# Acoustics_Power.net
KiCad netlist of a schematic drawn in Altium Designer
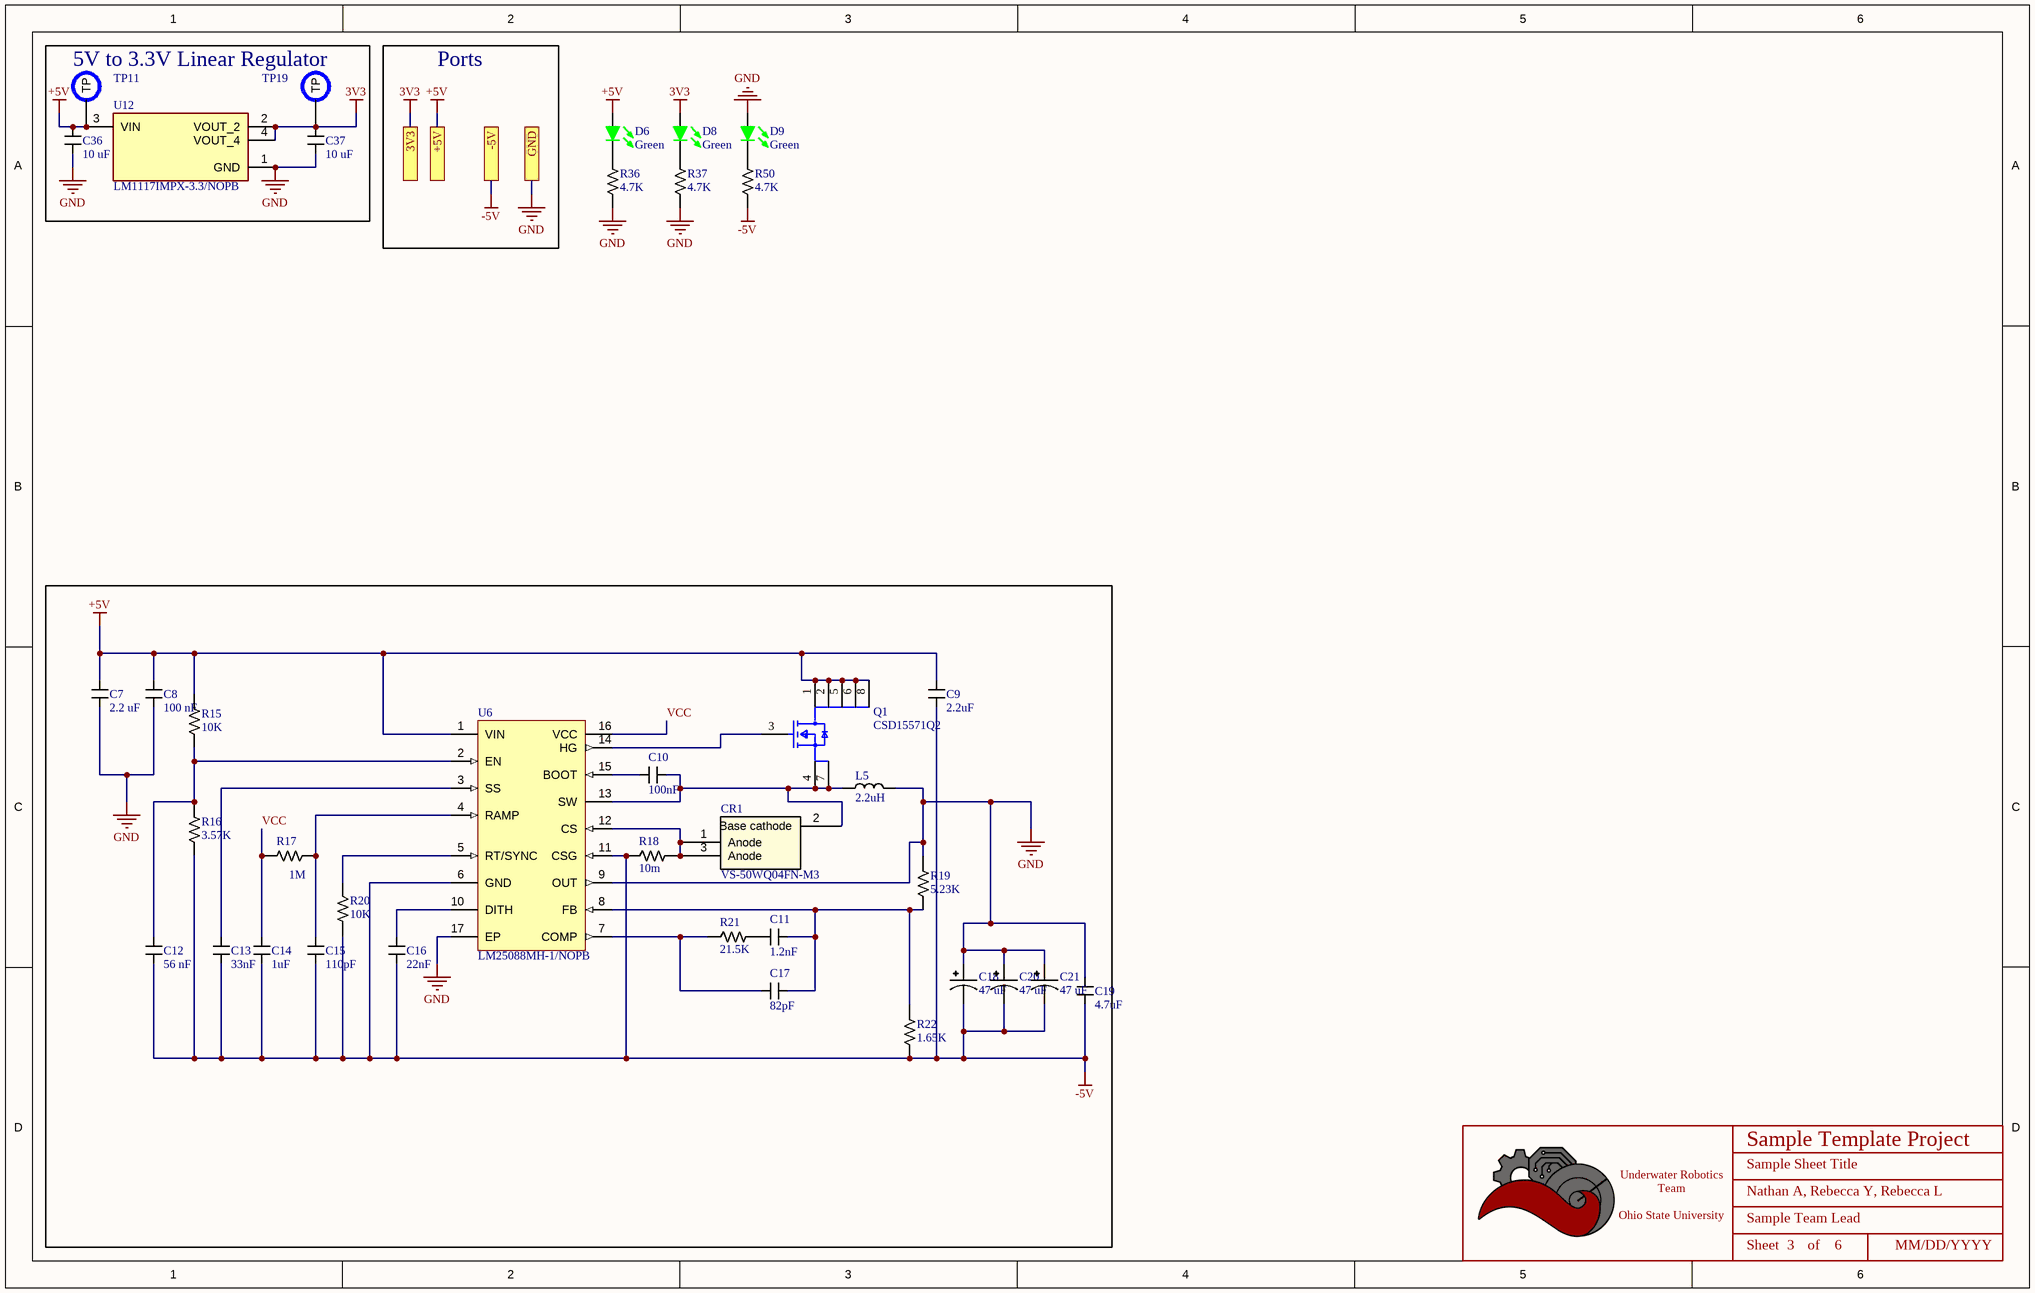
[diagram p0: [Acoustics] Power.SchDoc]

(export (version "E")
  (design (tool "Eeschema 10.0.6"))
  (components
    (comp (ref "C7")
      (value "2.2 uF")
      (footprint "CAPACITOR_0402")
      (description "Cap 1uF 16V +/-10%\r\nCeramic 0402")
      (fields
        (field (name "TOLERANCE") "+/- 10%")
        (field (name "VOLTAGE") "16V")
        (field (name "MADE BY") "Robert Pafford")
      )
      (libsource (lib "Capacitors") (part "CAPACITOR_1uF_0402"))
    )
    (comp (ref "C8")
      (value "100 nF")
      (footprint "CAPACITOR_0402")
      (description "Cap 1uF 16V +/-10%\r\nCeramic 0402")
      (fields
        (field (name "TOLERANCE") "+/- 10%")
        (field (name "VOLTAGE") "16V")
        (field (name "MADE BY") "Robert Pafford")
      )
      (libsource (lib "Capacitors") (part "CAPACITOR_1uF_0402"))
    )
    (comp (ref "C9")
      (value "2.2uF")
      (footprint "CAPACITOR_0402")
      (description "Cap 1uF 16V +/-10%\r\nCeramic 0402")
      (fields
        (field (name "TOLERANCE") "+/- 10%")
        (field (name "VOLTAGE") "16V")
        (field (name "MADE BY") "Robert Pafford")
      )
      (libsource (lib "Capacitors") (part "CAPACITOR_1uF_0402"))
    )
    (comp (ref "C10")
      (value "100nF")
      (footprint "CAPACITOR_0402")
      (description "Cap 1uF 16V +/-10%\r\nCeramic 0402")
      (fields
        (field (name "TOLERANCE") "+/- 10%")
        (field (name "VOLTAGE") "16V")
        (field (name "MADE BY") "Robert Pafford")
      )
      (libsource (lib "Capacitors") (part "CAPACITOR_1uF_0402"))
    )
    (comp (ref "C11")
      (value "1.2nF")
      (footprint "CAPACITOR_0402")
      (description "Cap 1uF 16V +/-10%\r\nCeramic 0402")
      (fields
        (field (name "TOLERANCE") "+/- 10%")
        (field (name "VOLTAGE") "16V")
        (field (name "MADE BY") "Robert Pafford")
      )
      (libsource (lib "Capacitors") (part "CAPACITOR_1uF_0402"))
    )
    (comp (ref "C12")
      (value "56 nF")
      (footprint "CAPACITOR_0402")
      (description "Cap 1uF 16V +/-10%\r\nCeramic 0402")
      (fields
        (field (name "TOLERANCE") "+/- 10%")
        (field (name "VOLTAGE") "16V")
        (field (name "MADE BY") "Robert Pafford")
      )
      (libsource (lib "Capacitors") (part "CAPACITOR_1uF_0402"))
    )
    (comp (ref "C13")
      (value "33nF")
      (footprint "CAPACITOR_0402")
      (description "Cap 1uF 16V +/-10%\r\nCeramic 0402")
      (fields
        (field (name "TOLERANCE") "+/- 10%")
        (field (name "VOLTAGE") "16V")
        (field (name "MADE BY") "Robert Pafford")
      )
      (libsource (lib "Capacitors") (part "CAPACITOR_1uF_0402"))
    )
    (comp (ref "C14")
      (value "1uF")
      (footprint "CAPACITOR_0402")
      (description "Cap 1uF 16V +/-10%\r\nCeramic 0402")
      (fields
        (field (name "TOLERANCE") "+/- 10%")
        (field (name "VOLTAGE") "16V")
        (field (name "MADE BY") "Robert Pafford")
      )
      (libsource (lib "Capacitors") (part "CAPACITOR_1uF_0402"))
    )
    (comp (ref "C15")
      (value "110pF")
      (footprint "CAPACITOR_0402")
      (description "Cap 1uF 16V +/-10%\r\nCeramic 0402")
      (fields
        (field (name "TOLERANCE") "+/- 10%")
        (field (name "VOLTAGE") "16V")
        (field (name "MADE BY") "Robert Pafford")
      )
      (libsource (lib "Capacitors") (part "CAPACITOR_1uF_0402"))
    )
    (comp (ref "C16")
      (value "22nF")
      (footprint "CAPACITOR_0402")
      (description "Cap 1uF 16V +/-10%\r\nCeramic 0402")
      (fields
        (field (name "TOLERANCE") "+/- 10%")
        (field (name "VOLTAGE") "16V")
        (field (name "MADE BY") "Robert Pafford")
      )
      (libsource (lib "Capacitors") (part "CAPACITOR_1uF_0402"))
    )
    (comp (ref "C17")
      (value "82pF")
      (footprint "CAPACITOR_0402")
      (description "Cap 1uF 16V +/-10%\r\nCeramic 0402")
      (fields
        (field (name "TOLERANCE") "+/- 10%")
        (field (name "VOLTAGE") "16V")
        (field (name "MADE BY") "Robert Pafford")
      )
      (libsource (lib "Capacitors") (part "CAPACITOR_1uF_0402"))
    )
    (comp (ref "C18")
      (value "10uF Tantalum 16V")
      (footprint "CAPACITOR_1206 - POLAR")
      (description "Cap 10uF 16V +/-20%\r\nTantalum 1206")
      (fields
        (field (name "TOLERANCE") "+/- 10%")
        (field (name "VOLTAGE") "16V")
        (field (name "VALUE (UF)") "47 uF")
        (field (name "MADE BY") "Dylan T")
      )
      (libsource (lib "Capacitors") (part "CAPACITOR_10uF_1206_Tantalum_1"))
    )
    (comp (ref "C19")
      (value "4.7uF")
      (footprint "CAPACITOR_0402")
      (description "Cap 1uF 16V +/-10%\r\nCeramic 0402")
      (fields
        (field (name "TOLERANCE") "+/- 10%")
        (field (name "VOLTAGE") "16V")
        (field (name "MADE BY") "Robert Pafford")
      )
      (libsource (lib "Capacitors") (part "CAPACITOR_1uF_0402"))
    )
    (comp (ref "C20")
      (value "10uF Tantalum 16V")
      (footprint "CAPACITOR_1206 - POLAR")
      (description "Cap 10uF 16V +/-20%\r\nTantalum 1206")
      (fields
        (field (name "TOLERANCE") "+/- 10%")
        (field (name "VOLTAGE") "16V")
        (field (name "VALUE (UF)") "47 uF")
        (field (name "MADE BY") "Dylan T")
      )
      (libsource (lib "Capacitors") (part "CAPACITOR_10uF_1206_Tantalum_1"))
    )
    (comp (ref "C21")
      (value "10uF Tantalum 16V")
      (footprint "CAPACITOR_1206 - POLAR")
      (description "Cap 10uF 16V +/-20%\r\nTantalum 1206")
      (fields
        (field (name "TOLERANCE") "+/- 10%")
        (field (name "VOLTAGE") "16V")
        (field (name "VALUE (UF)") "47 uF")
        (field (name "MADE BY") "Dylan T")
      )
      (libsource (lib "Capacitors") (part "CAPACITOR_10uF_1206_Tantalum_1"))
    )
    (comp (ref "C36")
      (value "10uF Ceramic 6.3V")
      (footprint "CAPACITOR_0603")
      (description "Cap 10uF 6.3V +/-20%\r\nCeramic 0603")
      (fields
        (field (name "TOLERANCE") "+/- 20%")
        (field (name "VOLTAGE") "6.3V")
        (field (name "VALUE (UF)") "10 uF")
        (field (name "MADE BY") "Flip B")
      )
      (libsource (lib "Capacitors") (part "CAPACITOR_10uF_0603"))
    )
    (comp (ref "C37")
      (value "10uF Ceramic 6.3V")
      (footprint "CAPACITOR_0603")
      (description "Cap 10uF 6.3V +/-20%\r\nCeramic 0603")
      (fields
        (field (name "TOLERANCE") "+/- 20%")
        (field (name "VOLTAGE") "6.3V")
        (field (name "VALUE (UF)") "10 uF")
        (field (name "MADE BY") "Flip B")
      )
      (libsource (lib "Capacitors") (part "CAPACITOR_10uF_0603"))
    )
    (comp (ref "CR1")
      (value "VS-50WQ04FN-M3")
      (footprint "D2PAK_VIS")
      (description "No Description Available")
      (libsource (lib "Diodes") (part "VS-50WQ04FN-M3"))
    )
    (comp (ref "D6")
      (value "IN-S63AT5G")
      (footprint "LED_0603")
      (description "LED Green Vf= 3V If = 0.005A\r\nIN-S63AT5G")
      (fields (field (name "COLOR") "Green") (field (name "MADE BY") "Robert Pafford"))
      (libsource (lib "Diodes") (part "LED_Green_0603_3V"))
    )
    (comp (ref "D8")
      (value "IN-S63AT5G")
      (footprint "LED_0603")
      (description "LED Green Vf= 3V If = 0.005A\r\nIN-S63AT5G")
      (fields (field (name "COLOR") "Green") (field (name "MADE BY") "Robert Pafford"))
      (libsource (lib "Diodes") (part "LED_Green_0603_3V"))
    )
    (comp (ref "D9")
      (value "IN-S63AT5G")
      (footprint "LED_0603")
      (description "LED Green Vf= 3V If = 0.005A\r\nIN-S63AT5G")
      (fields (field (name "COLOR") "Green") (field (name "MADE BY") "Robert Pafford"))
      (libsource (lib "Diodes") (part "LED_Green_0603_3V"))
    )
    (comp (ref "L5")
      (value "2.2uH")
      (footprint "INDUCTOR_0402")
      (description "15 nH Unshielded Multilayer Inductor 250 mA 600mOhm Max 0402 (1005 Metric)")
      (fields (field (name "TOLERANCE") "+/- 5%") (field (name "Comment") "FIXED IND 15NH 250MA 600MOHM SMD"))
      (libsource (lib "Inductors") (part "INDUCTOR_15nH_0402"))
    )
    (comp (ref "Q1")
      (value "CSD15571Q2")
      (footprint "FP-DQK0006C-MFG")
      (description "MOSFET N-CH 20V 22A 6SON")
      (libsource (lib "Altium Content Vault") (part "311c374e0721b15468b9837d6aab788"))
    )
    (comp (ref "R15")
      (value "1k Ohm 1% 1/16W")
      (footprint "RESISTOR_0402")
      (description "RES 1k OHM 1% 1/16W 0402")
      (fields
        (field (name "TOLERANCE") "+/- 1%")
        (field (name "VALUE  (OHMS)") "10K")
        (field (name "MADE BY") "Robert Pafford")
      )
      (libsource (lib "Resistors") (part "RESISTOR_1K_0402"))
    )
    (comp (ref "R16")
      (value "1k Ohm 1% 1/16W")
      (footprint "RESISTOR_0402")
      (description "RES 1k OHM 1% 1/16W 0402")
      (fields
        (field (name "TOLERANCE") "+/- 1%")
        (field (name "VALUE  (OHMS)") "3.57K")
        (field (name "MADE BY") "Robert Pafford")
      )
      (libsource (lib "Resistors") (part "RESISTOR_1K_0402"))
    )
    (comp (ref "R17")
      (value "1k Ohm 1% 1/16W")
      (footprint "RESISTOR_0402")
      (description "RES 1k OHM 1% 1/16W 0402")
      (fields
        (field (name "TOLERANCE") "+/- 1%")
        (field (name "VALUE  (OHMS)") "1M")
        (field (name "MADE BY") "Robert Pafford")
      )
      (libsource (lib "Resistors") (part "RESISTOR_1K_0402"))
    )
    (comp (ref "R18")
      (value "1k Ohm 1% 1/16W")
      (footprint "RESISTOR_0402")
      (description "RES 1k OHM 1% 1/16W 0402")
      (fields
        (field (name "TOLERANCE") "+/- 1%")
        (field (name "VALUE  (OHMS)") "10m")
        (field (name "MADE BY") "Robert Pafford")
      )
      (libsource (lib "Resistors") (part "RESISTOR_1K_0402"))
    )
    (comp (ref "R19")
      (value "1k Ohm 1% 1/16W")
      (footprint "RESISTOR_0402")
      (description "RES 1k OHM 1% 1/16W 0402")
      (fields
        (field (name "TOLERANCE") "+/- 1%")
        (field (name "VALUE  (OHMS)") "5.23K")
        (field (name "MADE BY") "Robert Pafford")
      )
      (libsource (lib "Resistors") (part "RESISTOR_1K_0402"))
    )
    (comp (ref "R20")
      (value "1k Ohm 1% 1/16W")
      (footprint "RESISTOR_0402")
      (description "RES 1k OHM 1% 1/16W 0402")
      (fields
        (field (name "TOLERANCE") "+/- 1%")
        (field (name "VALUE  (OHMS)") "10K")
        (field (name "MADE BY") "Robert Pafford")
      )
      (libsource (lib "Resistors") (part "RESISTOR_1K_0402"))
    )
    (comp (ref "R21")
      (value "1k Ohm 1% 1/16W")
      (footprint "RESISTOR_0402")
      (description "RES 1k OHM 1% 1/16W 0402")
      (fields
        (field (name "TOLERANCE") "+/- 1%")
        (field (name "VALUE  (OHMS)") "21.5K")
        (field (name "MADE BY") "Robert Pafford")
      )
      (libsource (lib "Resistors") (part "RESISTOR_1K_0402"))
    )
    (comp (ref "R22")
      (value "1k Ohm 1% 1/16W")
      (footprint "RESISTOR_0402")
      (description "RES 1k OHM 1% 1/16W 0402")
      (fields
        (field (name "TOLERANCE") "+/- 1%")
        (field (name "VALUE  (OHMS)") "1.65K")
        (field (name "MADE BY") "Robert Pafford")
      )
      (libsource (lib "Resistors") (part "RESISTOR_1K_0402"))
    )
    (comp (ref "R36")
      (value "4.7k Ohm 5% 1/10W")
      (footprint "RESISTOR_0603")
      (description "RES 4.7k OHM 5% 1/10W 0603")
      (fields
        (field (name "TOLERANCE") "+/- 5%")
        (field (name "VALUE  (OHMS)") "4.7K")
        (field (name "MADE BY") "Robert Pafford")
      )
      (libsource (lib "Resistors") (part "RESISTOR_4.7K_0603"))
    )
    (comp (ref "R37")
      (value "4.7k Ohm 5% 1/10W")
      (footprint "RESISTOR_0603")
      (description "RES 4.7k OHM 5% 1/10W 0603")
      (fields
        (field (name "TOLERANCE") "+/- 5%")
        (field (name "VALUE  (OHMS)") "4.7K")
        (field (name "MADE BY") "Robert Pafford")
      )
      (libsource (lib "Resistors") (part "RESISTOR_4.7K_0603"))
    )
    (comp (ref "R50")
      (value "4.7k Ohm 5% 1/10W")
      (footprint "RESISTOR_0603")
      (description "RES 4.7k OHM 5% 1/10W 0603")
      (fields
        (field (name "TOLERANCE") "+/- 5%")
        (field (name "VALUE  (OHMS)") "4.7K")
        (field (name "MADE BY") "Robert Pafford")
      )
      (libsource (lib "Resistors") (part "RESISTOR_4.7K_0603"))
    )
    (comp (ref "TP11")
      (value "PCB Test Point")
      (footprint "TESTPOINT_1.2MM")
      (fields (field (name "MADE BY") "Robert Pafford"))
      (libsource (lib "Connectors") (part "TESTPOINT"))
    )
    (comp (ref "TP19")
      (value "PCB Test Point")
      (footprint "TESTPOINT_1.2MM")
      (fields (field (name "MADE BY") "Robert Pafford"))
      (libsource (lib "Connectors") (part "TESTPOINT"))
    )
    (comp (ref "U6")
      (value "LM25088MH-1/NOPB")
      (footprint "PWP0016A_N")
      (description "Wide Input Range Non-Synchronous Buck Controller, 16-pin TSSOP-EP, Pb-Free")
      (fields (field (name "MANUFACTURER") "Texas Instruments"))
      (libsource (lib "Altium Content Vault") (part "PM-REG-LM25088-IL17"))
    )
    (comp (ref "U12")
      (value "LM1117IMPX-3.3/NOPB")
      (footprint "SOT-223-4")
      (description "800-mA 15-V linear voltage regulator 4-SOT-223 -40 to 125")
      (fields (field (name "MF") "Texas Instruments"))
      (libsource (lib "Integrated Circuits") (part "LM1117IMPX-3.3/NOPB"))
    )
  )
  (nets
    (net (code "1") (name "+5V") (class "Default")
      (node (ref "C36") (pin "1") (pinfunction "1_1") (pintype "passive"))
      (node (ref "C7") (pin "1") (pinfunction "1_1") (pintype "passive"))
      (node (ref "C8") (pin "1") (pinfunction "1_1") (pintype "passive"))
      (node (ref "C9") (pin "1") (pinfunction "1_1") (pintype "passive"))
      (node (ref "D6") (pin "1") (pinfunction "1_1") (pintype "passive"))
      (node (ref "Q1") (pin "1") (pinfunction "D_1") (pintype "passive"))
      (node (ref "Q1") (pin "2") (pinfunction "D_2") (pintype "passive"))
      (node (ref "Q1") (pin "5") (pinfunction "D_5") (pintype "passive"))
      (node (ref "Q1") (pin "6") (pinfunction "D_6") (pintype "passive"))
      (node (ref "Q1") (pin "8") (pinfunction "D_8") (pintype "passive"))
      (node (ref "R15") (pin "1") (pinfunction "1_1") (pintype "passive"))
      (node (ref "TP11") (pin "TP") (pinfunction "TP_TP") (pintype "passive"))
      (node (ref "U12") (pin "3") (pinfunction "VIN_3") (pintype "power_in"))
      (node (ref "U6") (pin "1") (pinfunction "VIN_1") (pintype "power_in"))
    )
    (net (code "2") (name "-5V") (class "Default")
      (node (ref "C12") (pin "2") (pinfunction "2_2") (pintype "passive"))
      (node (ref "C13") (pin "2") (pinfunction "2_2") (pintype "passive"))
      (node (ref "C14") (pin "2") (pinfunction "2_2") (pintype "passive"))
      (node (ref "C15") (pin "2") (pinfunction "2_2") (pintype "passive"))
      (node (ref "C16") (pin "2") (pinfunction "2_2") (pintype "passive"))
      (node (ref "C18") (pin "2") (pintype "passive"))
      (node (ref "C19") (pin "2") (pinfunction "2_2") (pintype "passive"))
      (node (ref "C20") (pin "2") (pintype "passive"))
      (node (ref "C21") (pin "2") (pintype "passive"))
      (node (ref "C9") (pin "2") (pinfunction "2_2") (pintype "passive"))
      (node (ref "R16") (pin "2") (pinfunction "2_2") (pintype "passive"))
      (node (ref "R18") (pin "2") (pinfunction "2_2") (pintype "passive"))
      (node (ref "R20") (pin "1") (pinfunction "1_1") (pintype "passive"))
      (node (ref "R22") (pin "2") (pinfunction "2_2") (pintype "passive"))
      (node (ref "R50") (pin "2") (pinfunction "2_2") (pintype "passive"))
      (node (ref "U6") (pin "11") (pinfunction "CSG_11") (pintype "input"))
      (node (ref "U6") (pin "6") (pinfunction "GND_6") (pintype "power_in"))
    )
    (net (code "3") (name "/VCC") (class "Default")
      (node (ref "C14") (pin "1") (pinfunction "1_1") (pintype "passive"))
      (node (ref "R17") (pin "1") (pinfunction "1_1") (pintype "passive"))
      (node (ref "U6") (pin "16") (pinfunction "VCC_16") (pintype "power_in"))
    )
    (net (code "4") (name "3V3") (class "Default")
      (node (ref "C37") (pin "1") (pinfunction "1_1") (pintype "passive"))
      (node (ref "D8") (pin "1") (pinfunction "1_1") (pintype "passive"))
      (node (ref "TP19") (pin "TP") (pinfunction "TP_TP") (pintype "passive"))
      (node (ref "U12") (pin "2") (pinfunction "VOUT_2_2") (pintype "power_in"))
      (node (ref "U12") (pin "4") (pinfunction "VOUT_4_4") (pintype "power_in"))
    )
    (net (code "5") (name "GND") (class "Default")
      (node (ref "C18") (pin "1") (pintype "passive"))
      (node (ref "C19") (pin "1") (pinfunction "1_1") (pintype "passive"))
      (node (ref "C20") (pin "1") (pintype "passive"))
      (node (ref "C21") (pin "1") (pintype "passive"))
      (node (ref "C36") (pin "2") (pinfunction "2_2") (pintype "passive"))
      (node (ref "C37") (pin "2") (pinfunction "2_2") (pintype "passive"))
      (node (ref "C7") (pin "2") (pinfunction "2_2") (pintype "passive"))
      (node (ref "C8") (pin "2") (pinfunction "2_2") (pintype "passive"))
      (node (ref "D9") (pin "1") (pinfunction "1_1") (pintype "passive"))
      (node (ref "L5") (pin "1") (pinfunction "1_1") (pintype "passive"))
      (node (ref "R19") (pin "1") (pinfunction "1_1") (pintype "passive"))
      (node (ref "R36") (pin "2") (pinfunction "2_2") (pintype "passive"))
      (node (ref "R37") (pin "2") (pinfunction "2_2") (pintype "passive"))
      (node (ref "U12") (pin "1") (pinfunction "GND_1") (pintype "power_in"))
      (node (ref "U6") (pin "17") (pinfunction "EP_17") (pintype "power_in"))
      (node (ref "U6") (pin "9") (pinfunction "OUT_9") (pintype "output"))
    )
    (net (code "6") (name "Net-(C11-Pad2)") (class "Default")
      (node (ref "C11") (pin "2") (pinfunction "2_2") (pintype "passive"))
      (node (ref "R21") (pin "1") (pinfunction "1_1") (pintype "passive"))
    )
    (net (code "7") (name "Net-(CR1-Base_cathode)") (class "Default")
      (node (ref "C10") (pin "1") (pinfunction "1_1") (pintype "passive"))
      (node (ref "CR1") (pin "2") (pinfunction "Base_cathode_2") (pintype "passive"))
      (node (ref "L5") (pin "2") (pinfunction "2_2") (pintype "passive"))
      (node (ref "Q1") (pin "4") (pinfunction "S_4") (pintype "passive"))
      (node (ref "Q1") (pin "7") (pinfunction "S_7") (pintype "passive"))
      (node (ref "U6") (pin "13") (pinfunction "SW_13") (pintype "passive"))
    )
    (net (code "8") (name "Net-(D6-Pad2)") (class "Default")
      (node (ref "D6") (pin "2") (pinfunction "2_2") (pintype "passive"))
      (node (ref "R36") (pin "1") (pinfunction "1_1") (pintype "passive"))
    )
    (net (code "9") (name "Net-(D8-Pad2)") (class "Default")
      (node (ref "D8") (pin "2") (pinfunction "2_2") (pintype "passive"))
      (node (ref "R37") (pin "1") (pinfunction "1_1") (pintype "passive"))
    )
    (net (code "10") (name "Net-(D9-Pad2)") (class "Default")
      (node (ref "D9") (pin "2") (pinfunction "2_2") (pintype "passive"))
      (node (ref "R50") (pin "1") (pinfunction "1_1") (pintype "passive"))
    )
    (net (code "11") (name "Net-(Q1-G)") (class "Default")
      (node (ref "Q1") (pin "3") (pinfunction "G_3") (pintype "passive"))
      (node (ref "U6") (pin "14") (pinfunction "HG_14") (pintype "output"))
    )
    (net (code "12") (name "Net-(U6-BOOT)") (class "Default")
      (node (ref "C10") (pin "2") (pinfunction "2_2") (pintype "passive"))
      (node (ref "U6") (pin "15") (pinfunction "BOOT_15") (pintype "input"))
    )
    (net (code "13") (name "Net-(U6-COMP)") (class "Default")
      (node (ref "C17") (pin "2") (pinfunction "2_2") (pintype "passive"))
      (node (ref "R21") (pin "2") (pinfunction "2_2") (pintype "passive"))
      (node (ref "U6") (pin "7") (pinfunction "COMP_7") (pintype "output"))
    )
    (net (code "14") (name "Net-(U6-CS)") (class "Default")
      (node (ref "CR1") (pin "1") (pinfunction "Anode_1") (pintype "passive"))
      (node (ref "CR1") (pin "3") (pinfunction "Anode_3") (pintype "passive"))
      (node (ref "R18") (pin "1") (pinfunction "1_1") (pintype "passive"))
      (node (ref "U6") (pin "12") (pinfunction "CS_12") (pintype "input"))
    )
    (net (code "15") (name "Net-(U6-DITH)") (class "Default")
      (node (ref "C16") (pin "1") (pinfunction "1_1") (pintype "passive"))
      (node (ref "U6") (pin "10") (pinfunction "DITH_10") (pintype "power_in"))
    )
    (net (code "16") (name "Net-(U6-EN)") (class "Default")
      (node (ref "C12") (pin "1") (pinfunction "1_1") (pintype "passive"))
      (node (ref "R15") (pin "2") (pinfunction "2_2") (pintype "passive"))
      (node (ref "R16") (pin "1") (pinfunction "1_1") (pintype "passive"))
      (node (ref "U6") (pin "2") (pinfunction "EN_2") (pintype "input"))
    )
    (net (code "17") (name "Net-(U6-FB)") (class "Default")
      (node (ref "C11") (pin "1") (pinfunction "1_1") (pintype "passive"))
      (node (ref "C17") (pin "1") (pinfunction "1_1") (pintype "passive"))
      (node (ref "R19") (pin "2") (pinfunction "2_2") (pintype "passive"))
      (node (ref "R22") (pin "1") (pinfunction "1_1") (pintype "passive"))
      (node (ref "U6") (pin "8") (pinfunction "FB_8") (pintype "input"))
    )
    (net (code "18") (name "Net-(U6-RAMP)") (class "Default")
      (node (ref "C15") (pin "1") (pinfunction "1_1") (pintype "passive"))
      (node (ref "R17") (pin "2") (pinfunction "2_2") (pintype "passive"))
      (node (ref "U6") (pin "4") (pinfunction "RAMP_4") (pintype "input"))
    )
    (net (code "19") (name "Net-(U6-RT{slash}SYNC)") (class "Default")
      (node (ref "R20") (pin "2") (pinfunction "2_2") (pintype "passive"))
      (node (ref "U6") (pin "5") (pinfunction "RT/SYNC_5") (pintype "input"))
    )
    (net (code "20") (name "Net-(U6-SS)") (class "Default")
      (node (ref "C13") (pin "1") (pinfunction "1_1") (pintype "passive"))
      (node (ref "U6") (pin "3") (pinfunction "SS_3") (pintype "input"))
    )
  )
)
